# Ilumitunes-IR-String-Controller-v13.net
KiCad netlist of a schematic drawn in EAGLE
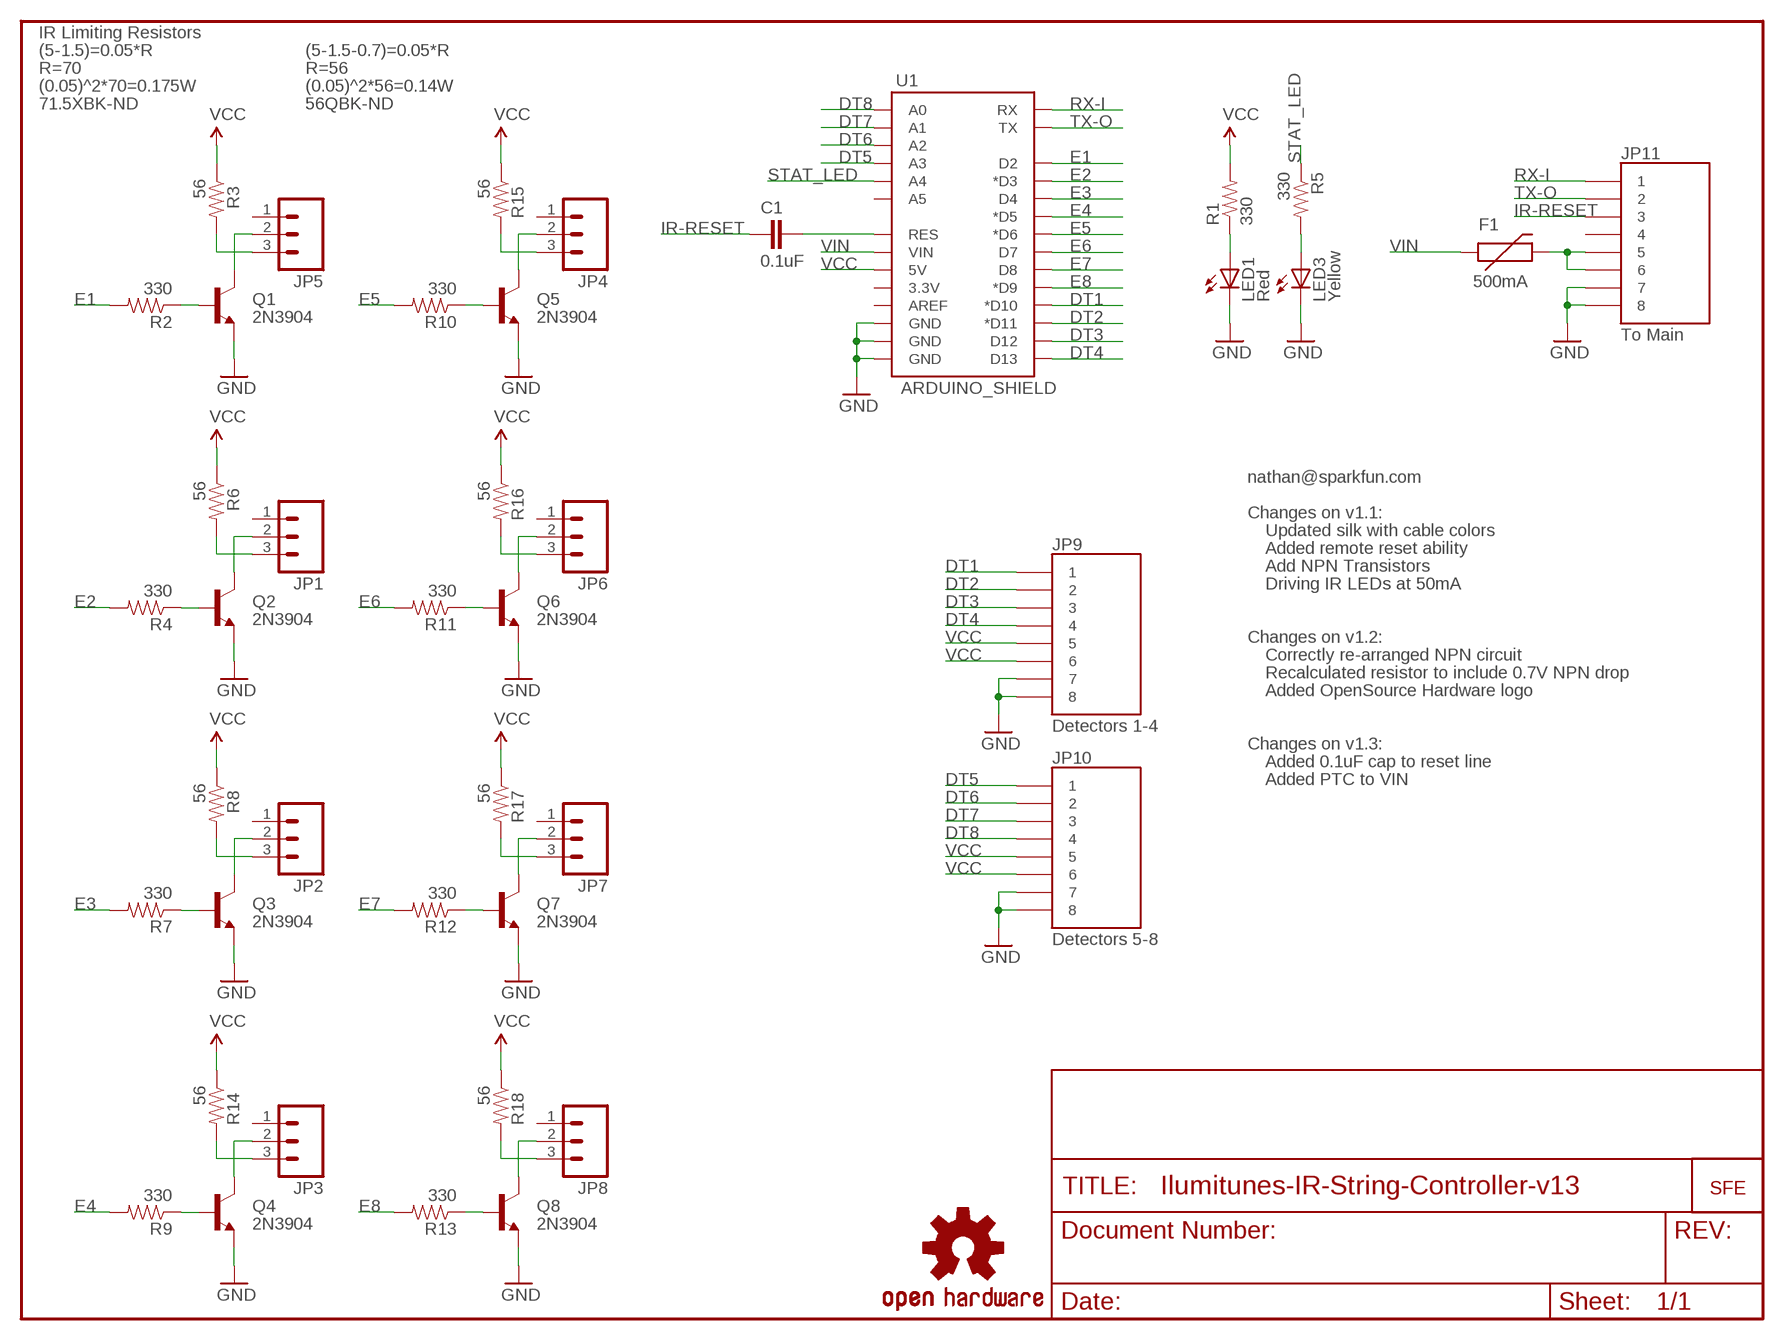
[diagram p0: schematic, sheet 1]

(export (version "E")
  (design (tool "Eeschema 10.0.6"))
  (components
    (comp (ref "C1")
      (value "0.1uF")
      (footprint "eagle-import:CAP-PTH-SMALL2")
      (libsource (lib "eagle-import") (part "CAPPTH2"))
    )
    (comp (ref "F1")
      (value "500mA")
      (footprint "eagle-import:PTC")
      (libsource (lib "eagle-import") (part "PTCPTH"))
    )
    (comp (ref "JP1")
      (value "M03JST-PTH-VERT")
      (footprint "eagle-import:JST-3-PTH-VERT")
      (libsource (lib "eagle-import") (part "M03JST-PTH-VERT"))
    )
    (comp (ref "JP2")
      (value "M03JST-PTH-VERT")
      (footprint "eagle-import:JST-3-PTH-VERT")
      (libsource (lib "eagle-import") (part "M03JST-PTH-VERT"))
    )
    (comp (ref "JP3")
      (value "M03JST-PTH-VERT")
      (footprint "eagle-import:JST-3-PTH-VERT")
      (libsource (lib "eagle-import") (part "M03JST-PTH-VERT"))
    )
    (comp (ref "JP4")
      (value "M03JST-PTH-VERT")
      (footprint "eagle-import:JST-3-PTH-VERT")
      (libsource (lib "eagle-import") (part "M03JST-PTH-VERT"))
    )
    (comp (ref "JP5")
      (value "M03JST-PTH-VERT")
      (footprint "eagle-import:JST-3-PTH-VERT")
      (libsource (lib "eagle-import") (part "M03JST-PTH-VERT"))
    )
    (comp (ref "JP6")
      (value "M03JST-PTH-VERT")
      (footprint "eagle-import:JST-3-PTH-VERT")
      (libsource (lib "eagle-import") (part "M03JST-PTH-VERT"))
    )
    (comp (ref "JP7")
      (value "M03JST-PTH-VERT")
      (footprint "eagle-import:JST-3-PTH-VERT")
      (libsource (lib "eagle-import") (part "M03JST-PTH-VERT"))
    )
    (comp (ref "JP8")
      (value "M03JST-PTH-VERT")
      (footprint "eagle-import:JST-3-PTH-VERT")
      (libsource (lib "eagle-import") (part "M03JST-PTH-VERT"))
    )
    (comp (ref "JP9")
      (value "Detectors 1-4")
      (footprint "eagle-import:RJ45-8")
      (libsource (lib "eagle-import") (part "RJ45-8PTH"))
    )
    (comp (ref "JP10")
      (value "Detectors 5-8")
      (footprint "eagle-import:RJ45-8")
      (libsource (lib "eagle-import") (part "RJ45-8PTH"))
    )
    (comp (ref "JP11")
      (value "To Main")
      (footprint "eagle-import:RJ45-8")
      (libsource (lib "eagle-import") (part "RJ45-8PTH"))
    )
    (comp (ref "LED1")
      (value "Red")
      (footprint "eagle-import:LED5MM")
      (libsource (lib "eagle-import") (part "LED5MM"))
    )
    (comp (ref "LED3")
      (value "Yellow")
      (footprint "eagle-import:LED5MM")
      (libsource (lib "eagle-import") (part "LED5MM"))
    )
    (comp (ref "Q1")
      (value "2N3904")
      (footprint "eagle-import:TO-92")
      (libsource (lib "eagle-import") (part "TRANSISTOR_NPNTO92"))
    )
    (comp (ref "Q2")
      (value "2N3904")
      (footprint "eagle-import:TO-92")
      (libsource (lib "eagle-import") (part "TRANSISTOR_NPNTO92"))
    )
    (comp (ref "Q3")
      (value "2N3904")
      (footprint "eagle-import:TO-92")
      (libsource (lib "eagle-import") (part "TRANSISTOR_NPNTO92"))
    )
    (comp (ref "Q4")
      (value "2N3904")
      (footprint "eagle-import:TO-92")
      (libsource (lib "eagle-import") (part "TRANSISTOR_NPNTO92"))
    )
    (comp (ref "Q5")
      (value "2N3904")
      (footprint "eagle-import:TO-92")
      (libsource (lib "eagle-import") (part "TRANSISTOR_NPNTO92"))
    )
    (comp (ref "Q6")
      (value "2N3904")
      (footprint "eagle-import:TO-92")
      (libsource (lib "eagle-import") (part "TRANSISTOR_NPNTO92"))
    )
    (comp (ref "Q7")
      (value "2N3904")
      (footprint "eagle-import:TO-92")
      (libsource (lib "eagle-import") (part "TRANSISTOR_NPNTO92"))
    )
    (comp (ref "Q8")
      (value "2N3904")
      (footprint "eagle-import:TO-92")
      (libsource (lib "eagle-import") (part "TRANSISTOR_NPNTO92"))
    )
    (comp (ref "R1")
      (value "330")
      (footprint "eagle-import:AXIAL-0.3")
      (libsource (lib "eagle-import") (part "RESISTORAXIAL-0.3"))
    )
    (comp (ref "R2")
      (value "330")
      (footprint "eagle-import:AXIAL-0.3")
      (libsource (lib "eagle-import") (part "RESISTORAXIAL-0.3"))
    )
    (comp (ref "R3")
      (value "56")
      (footprint "eagle-import:AXIAL-0.3")
      (libsource (lib "eagle-import") (part "RESISTORAXIAL-0.3"))
    )
    (comp (ref "R4")
      (value "330")
      (footprint "eagle-import:AXIAL-0.3")
      (libsource (lib "eagle-import") (part "RESISTORAXIAL-0.3"))
    )
    (comp (ref "R5")
      (value "330")
      (footprint "eagle-import:AXIAL-0.3")
      (libsource (lib "eagle-import") (part "RESISTORAXIAL-0.3"))
    )
    (comp (ref "R6")
      (value "56")
      (footprint "eagle-import:AXIAL-0.3")
      (libsource (lib "eagle-import") (part "RESISTORAXIAL-0.3"))
    )
    (comp (ref "R7")
      (value "330")
      (footprint "eagle-import:AXIAL-0.3")
      (libsource (lib "eagle-import") (part "RESISTORAXIAL-0.3"))
    )
    (comp (ref "R8")
      (value "56")
      (footprint "eagle-import:AXIAL-0.3")
      (libsource (lib "eagle-import") (part "RESISTORAXIAL-0.3"))
    )
    (comp (ref "R9")
      (value "330")
      (footprint "eagle-import:AXIAL-0.3")
      (libsource (lib "eagle-import") (part "RESISTORAXIAL-0.3"))
    )
    (comp (ref "R10")
      (value "330")
      (footprint "eagle-import:AXIAL-0.3")
      (libsource (lib "eagle-import") (part "RESISTORAXIAL-0.3"))
    )
    (comp (ref "R11")
      (value "330")
      (footprint "eagle-import:AXIAL-0.3")
      (libsource (lib "eagle-import") (part "RESISTORAXIAL-0.3"))
    )
    (comp (ref "R12")
      (value "330")
      (footprint "eagle-import:AXIAL-0.3")
      (libsource (lib "eagle-import") (part "RESISTORAXIAL-0.3"))
    )
    (comp (ref "R13")
      (value "330")
      (footprint "eagle-import:AXIAL-0.3")
      (libsource (lib "eagle-import") (part "RESISTORAXIAL-0.3"))
    )
    (comp (ref "R14")
      (value "56")
      (footprint "eagle-import:AXIAL-0.3")
      (libsource (lib "eagle-import") (part "RESISTORAXIAL-0.3"))
    )
    (comp (ref "R15")
      (value "56")
      (footprint "eagle-import:AXIAL-0.3")
      (libsource (lib "eagle-import") (part "RESISTORAXIAL-0.3"))
    )
    (comp (ref "R16")
      (value "56")
      (footprint "eagle-import:AXIAL-0.3")
      (libsource (lib "eagle-import") (part "RESISTORAXIAL-0.3"))
    )
    (comp (ref "R17")
      (value "56")
      (footprint "eagle-import:AXIAL-0.3")
      (libsource (lib "eagle-import") (part "RESISTORAXIAL-0.3"))
    )
    (comp (ref "R18")
      (value "56")
      (footprint "eagle-import:AXIAL-0.3")
      (libsource (lib "eagle-import") (part "RESISTORAXIAL-0.3"))
    )
    (comp (ref "U$1")
      (value "LOGO-SFENEW")
      (footprint "eagle-import:SFE-NEW-WEBLOGO")
      (libsource (lib "eagle-import") (part "LOGO-SFENEW"))
    )
    (comp (ref "U$3")
      (value "OSHW-LOGOS")
      (footprint "eagle-import:OSHW-LOGO-S")
      (libsource (lib "eagle-import") (part "OSHW-LOGOS"))
    )
    (comp (ref "U1")
      (value "ARDUINO_SHIELD")
      (footprint "eagle-import:DUEMILANOVE_SHIELD_NOHOLES")
      (libsource (lib "eagle-import") (part "ARDUINO_SHIELDNOHOLES"))
    )
  )
  (nets
    (net (code "1") (name "/DT1") (class "Default")
      (node (ref "JP9") (pin "1") (pinfunction "1_1") (pintype "bidirectional"))
      (node (ref "U1") (pin "D10") (pinfunction "*D10_D10") (pintype "bidirectional"))
    )
    (net (code "2") (name "/DT2") (class "Default")
      (node (ref "JP9") (pin "2") (pinfunction "2_2") (pintype "bidirectional"))
      (node (ref "U1") (pin "D11") (pinfunction "*D11_D11") (pintype "bidirectional"))
    )
    (net (code "3") (name "/DT3") (class "Default")
      (node (ref "JP9") (pin "3") (pinfunction "3_3") (pintype "bidirectional"))
      (node (ref "U1") (pin "D12") (pinfunction "D12_D12") (pintype "bidirectional"))
    )
    (net (code "4") (name "/DT4") (class "Default")
      (node (ref "JP9") (pin "4") (pinfunction "4_4") (pintype "bidirectional"))
      (node (ref "U1") (pin "D13") (pinfunction "D13_D13") (pintype "bidirectional"))
    )
    (net (code "5") (name "/DT5") (class "Default")
      (node (ref "JP10") (pin "1") (pinfunction "1_1") (pintype "bidirectional"))
      (node (ref "U1") (pin "A3") (pinfunction "A3_A3") (pintype "bidirectional"))
    )
    (net (code "6") (name "/DT6") (class "Default")
      (node (ref "JP10") (pin "2") (pinfunction "2_2") (pintype "bidirectional"))
      (node (ref "U1") (pin "A2") (pinfunction "A2_A2") (pintype "bidirectional"))
    )
    (net (code "7") (name "/DT7") (class "Default")
      (node (ref "JP10") (pin "3") (pinfunction "3_3") (pintype "bidirectional"))
      (node (ref "U1") (pin "A1") (pinfunction "A1_A1") (pintype "bidirectional"))
    )
    (net (code "8") (name "/DT8") (class "Default")
      (node (ref "JP10") (pin "4") (pinfunction "4_4") (pintype "bidirectional"))
      (node (ref "U1") (pin "A0") (pinfunction "A0_A0") (pintype "bidirectional"))
    )
    (net (code "9") (name "/E1") (class "Default")
      (node (ref "R2") (pin "P$2") (pinfunction "2_P$2") (pintype "passive"))
      (node (ref "U1") (pin "D2") (pinfunction "D2_D2") (pintype "bidirectional"))
    )
    (net (code "10") (name "/E2") (class "Default")
      (node (ref "R4") (pin "P$2") (pinfunction "2_P$2") (pintype "passive"))
      (node (ref "U1") (pin "D3") (pinfunction "*D3_D3") (pintype "bidirectional"))
    )
    (net (code "11") (name "/E3") (class "Default")
      (node (ref "R7") (pin "P$2") (pinfunction "2_P$2") (pintype "passive"))
      (node (ref "U1") (pin "D4") (pinfunction "D4_D4") (pintype "bidirectional"))
    )
    (net (code "12") (name "/E4") (class "Default")
      (node (ref "R9") (pin "P$2") (pinfunction "2_P$2") (pintype "passive"))
      (node (ref "U1") (pin "D5") (pinfunction "*D5_D5") (pintype "bidirectional"))
    )
    (net (code "13") (name "/E5") (class "Default")
      (node (ref "R10") (pin "P$2") (pinfunction "2_P$2") (pintype "passive"))
      (node (ref "U1") (pin "D6") (pinfunction "*D6_D6") (pintype "bidirectional"))
    )
    (net (code "14") (name "/E6") (class "Default")
      (node (ref "R11") (pin "P$2") (pinfunction "2_P$2") (pintype "passive"))
      (node (ref "U1") (pin "D7") (pinfunction "D7_D7") (pintype "bidirectional"))
    )
    (net (code "15") (name "/E7") (class "Default")
      (node (ref "R12") (pin "P$2") (pinfunction "2_P$2") (pintype "passive"))
      (node (ref "U1") (pin "D8") (pinfunction "D8_D8") (pintype "bidirectional"))
    )
    (net (code "16") (name "/E8") (class "Default")
      (node (ref "R13") (pin "P$2") (pinfunction "2_P$2") (pintype "passive"))
      (node (ref "U1") (pin "D9") (pinfunction "*D9_D9") (pintype "bidirectional"))
    )
    (net (code "17") (name "/IR-RESET") (class "Default")
      (node (ref "C1") (pin "1") (pinfunction "1_1") (pintype "passive"))
      (node (ref "JP11") (pin "3") (pinfunction "3_3") (pintype "bidirectional"))
    )
    (net (code "18") (name "/RX-I") (class "Default")
      (node (ref "JP11") (pin "1") (pinfunction "1_1") (pintype "bidirectional"))
      (node (ref "U1") (pin "RX") (pinfunction "RX_RX") (pintype "bidirectional"))
    )
    (net (code "19") (name "/STAT_LED") (class "Default")
      (node (ref "R5") (pin "P$1") (pinfunction "1_P$1") (pintype "passive"))
      (node (ref "U1") (pin "A4") (pinfunction "A4_A4") (pintype "bidirectional"))
    )
    (net (code "20") (name "/TX-O") (class "Default")
      (node (ref "JP11") (pin "2") (pinfunction "2_2") (pintype "bidirectional"))
      (node (ref "U1") (pin "TX") (pinfunction "TX_TX") (pintype "bidirectional"))
    )
    (net (code "21") (name "/VIN") (class "Default")
      (node (ref "F1") (pin "P$1") (pinfunction "1_P$1") (pintype "bidirectional"))
      (node (ref "U1") (pin "VIN") (pinfunction "VIN_VIN") (pintype "bidirectional"))
    )
    (net (code "22") (name "GND") (class "Default")
      (node (ref "JP10") (pin "7") (pinfunction "7_7") (pintype "bidirectional"))
      (node (ref "JP10") (pin "8") (pinfunction "8_8") (pintype "bidirectional"))
      (node (ref "JP11") (pin "7") (pinfunction "7_7") (pintype "bidirectional"))
      (node (ref "JP11") (pin "8") (pinfunction "8_8") (pintype "bidirectional"))
      (node (ref "JP9") (pin "7") (pinfunction "7_7") (pintype "bidirectional"))
      (node (ref "JP9") (pin "8") (pinfunction "8_8") (pintype "bidirectional"))
      (node (ref "LED1") (pin "K") (pinfunction "C_K") (pintype "passive"))
      (node (ref "LED3") (pin "K") (pinfunction "C_K") (pintype "passive"))
      (node (ref "Q1") (pin "1") (pinfunction "E_1") (pintype "passive"))
      (node (ref "Q2") (pin "1") (pinfunction "E_1") (pintype "passive"))
      (node (ref "Q3") (pin "1") (pinfunction "E_1") (pintype "passive"))
      (node (ref "Q4") (pin "1") (pinfunction "E_1") (pintype "passive"))
      (node (ref "Q5") (pin "1") (pinfunction "E_1") (pintype "passive"))
      (node (ref "Q6") (pin "1") (pinfunction "E_1") (pintype "passive"))
      (node (ref "Q7") (pin "1") (pinfunction "E_1") (pintype "passive"))
      (node (ref "Q8") (pin "1") (pinfunction "E_1") (pintype "passive"))
      (node (ref "U1") (pin "GND@0") (pinfunction "GND_GND@0") (pintype "bidirectional"))
      (node (ref "U1") (pin "GND@1") (pinfunction "GND_GND@1") (pintype "bidirectional"))
      (node (ref "U1") (pin "GND@2") (pinfunction "GND_GND@2") (pintype "bidirectional"))
    )
    (net (code "23") (name "Net-(C1-Pad2)") (class "Default")
      (node (ref "C1") (pin "2") (pinfunction "2_2") (pintype "passive"))
      (node (ref "U1") (pin "RES") (pinfunction "RES_RES") (pintype "bidirectional"))
    )
    (net (code "24") (name "Net-(F1-2)") (class "Default")
      (node (ref "F1") (pin "P$2") (pinfunction "2_P$2") (pintype "bidirectional"))
      (node (ref "JP11") (pin "5") (pinfunction "5_5") (pintype "bidirectional"))
      (node (ref "JP11") (pin "6") (pinfunction "6_6") (pintype "bidirectional"))
    )
    (net (code "25") (name "Net-(Q1-B)") (class "Default")
      (node (ref "Q1") (pin "2") (pinfunction "B_2") (pintype "passive"))
      (node (ref "R2") (pin "P$1") (pinfunction "1_P$1") (pintype "passive"))
    )
    (net (code "26") (name "Net-(Q1-C)") (class "Default")
      (node (ref "JP5") (pin "2") (pinfunction "2_2") (pintype "passive"))
      (node (ref "Q1") (pin "3") (pinfunction "C_3") (pintype "passive"))
    )
    (net (code "27") (name "Net-(Q2-B)") (class "Default")
      (node (ref "Q2") (pin "2") (pinfunction "B_2") (pintype "passive"))
      (node (ref "R4") (pin "P$1") (pinfunction "1_P$1") (pintype "passive"))
    )
    (net (code "28") (name "Net-(Q2-C)") (class "Default")
      (node (ref "JP1") (pin "2") (pinfunction "2_2") (pintype "passive"))
      (node (ref "Q2") (pin "3") (pinfunction "C_3") (pintype "passive"))
    )
    (net (code "29") (name "Net-(Q3-B)") (class "Default")
      (node (ref "Q3") (pin "2") (pinfunction "B_2") (pintype "passive"))
      (node (ref "R7") (pin "P$1") (pinfunction "1_P$1") (pintype "passive"))
    )
    (net (code "30") (name "Net-(Q3-C)") (class "Default")
      (node (ref "JP2") (pin "2") (pinfunction "2_2") (pintype "passive"))
      (node (ref "Q3") (pin "3") (pinfunction "C_3") (pintype "passive"))
    )
    (net (code "31") (name "Net-(Q4-B)") (class "Default")
      (node (ref "Q4") (pin "2") (pinfunction "B_2") (pintype "passive"))
      (node (ref "R9") (pin "P$1") (pinfunction "1_P$1") (pintype "passive"))
    )
    (net (code "32") (name "Net-(Q4-C)") (class "Default")
      (node (ref "JP3") (pin "2") (pinfunction "2_2") (pintype "passive"))
      (node (ref "Q4") (pin "3") (pinfunction "C_3") (pintype "passive"))
    )
    (net (code "33") (name "Net-(Q5-B)") (class "Default")
      (node (ref "Q5") (pin "2") (pinfunction "B_2") (pintype "passive"))
      (node (ref "R10") (pin "P$1") (pinfunction "1_P$1") (pintype "passive"))
    )
    (net (code "34") (name "Net-(Q5-C)") (class "Default")
      (node (ref "JP4") (pin "2") (pinfunction "2_2") (pintype "passive"))
      (node (ref "Q5") (pin "3") (pinfunction "C_3") (pintype "passive"))
    )
    (net (code "35") (name "Net-(Q6-B)") (class "Default")
      (node (ref "Q6") (pin "2") (pinfunction "B_2") (pintype "passive"))
      (node (ref "R11") (pin "P$1") (pinfunction "1_P$1") (pintype "passive"))
    )
    (net (code "36") (name "Net-(Q6-C)") (class "Default")
      (node (ref "JP6") (pin "2") (pinfunction "2_2") (pintype "passive"))
      (node (ref "Q6") (pin "3") (pinfunction "C_3") (pintype "passive"))
    )
    (net (code "37") (name "Net-(Q7-B)") (class "Default")
      (node (ref "Q7") (pin "2") (pinfunction "B_2") (pintype "passive"))
      (node (ref "R12") (pin "P$1") (pinfunction "1_P$1") (pintype "passive"))
    )
    (net (code "38") (name "Net-(Q7-C)") (class "Default")
      (node (ref "JP7") (pin "2") (pinfunction "2_2") (pintype "passive"))
      (node (ref "Q7") (pin "3") (pinfunction "C_3") (pintype "passive"))
    )
    (net (code "39") (name "Net-(Q8-B)") (class "Default")
      (node (ref "Q8") (pin "2") (pinfunction "B_2") (pintype "passive"))
      (node (ref "R13") (pin "P$1") (pinfunction "1_P$1") (pintype "passive"))
    )
    (net (code "40") (name "Net-(Q8-C)") (class "Default")
      (node (ref "JP8") (pin "2") (pinfunction "2_2") (pintype "passive"))
      (node (ref "Q8") (pin "3") (pinfunction "C_3") (pintype "passive"))
    )
    (net (code "41") (name "Net-(R1-1)") (class "Default")
      (node (ref "LED1") (pin "A") (pinfunction "A_A") (pintype "passive"))
      (node (ref "R1") (pin "P$1") (pinfunction "1_P$1") (pintype "passive"))
    )
    (net (code "42") (name "Net-(R3-2)") (class "Default")
      (node (ref "JP5") (pin "3") (pinfunction "3_3") (pintype "passive"))
      (node (ref "R3") (pin "P$2") (pinfunction "2_P$2") (pintype "passive"))
    )
    (net (code "43") (name "Net-(R5-2)") (class "Default")
      (node (ref "LED3") (pin "A") (pinfunction "A_A") (pintype "passive"))
      (node (ref "R5") (pin "P$2") (pinfunction "2_P$2") (pintype "passive"))
    )
    (net (code "44") (name "Net-(R6-2)") (class "Default")
      (node (ref "JP1") (pin "3") (pinfunction "3_3") (pintype "passive"))
      (node (ref "R6") (pin "P$2") (pinfunction "2_P$2") (pintype "passive"))
    )
    (net (code "45") (name "Net-(R8-2)") (class "Default")
      (node (ref "JP2") (pin "3") (pinfunction "3_3") (pintype "passive"))
      (node (ref "R8") (pin "P$2") (pinfunction "2_P$2") (pintype "passive"))
    )
    (net (code "46") (name "Net-(R14-2)") (class "Default")
      (node (ref "JP3") (pin "3") (pinfunction "3_3") (pintype "passive"))
      (node (ref "R14") (pin "P$2") (pinfunction "2_P$2") (pintype "passive"))
    )
    (net (code "47") (name "Net-(R15-2)") (class "Default")
      (node (ref "JP4") (pin "3") (pinfunction "3_3") (pintype "passive"))
      (node (ref "R15") (pin "P$2") (pinfunction "2_P$2") (pintype "passive"))
    )
    (net (code "48") (name "Net-(R16-2)") (class "Default")
      (node (ref "JP6") (pin "3") (pinfunction "3_3") (pintype "passive"))
      (node (ref "R16") (pin "P$2") (pinfunction "2_P$2") (pintype "passive"))
    )
    (net (code "49") (name "Net-(R17-2)") (class "Default")
      (node (ref "JP7") (pin "3") (pinfunction "3_3") (pintype "passive"))
      (node (ref "R17") (pin "P$2") (pinfunction "2_P$2") (pintype "passive"))
    )
    (net (code "50") (name "Net-(R18-2)") (class "Default")
      (node (ref "JP8") (pin "3") (pinfunction "3_3") (pintype "passive"))
      (node (ref "R18") (pin "P$2") (pinfunction "2_P$2") (pintype "passive"))
    )
    (net (code "51") (name "VCC") (class "Default")
      (node (ref "JP10") (pin "5") (pinfunction "5_5") (pintype "bidirectional"))
      (node (ref "JP10") (pin "6") (pinfunction "6_6") (pintype "bidirectional"))
      (node (ref "JP9") (pin "5") (pinfunction "5_5") (pintype "bidirectional"))
      (node (ref "JP9") (pin "6") (pinfunction "6_6") (pintype "bidirectional"))
      (node (ref "R1") (pin "P$2") (pinfunction "2_P$2") (pintype "passive"))
      (node (ref "R14") (pin "P$1") (pinfunction "1_P$1") (pintype "passive"))
      (node (ref "R15") (pin "P$1") (pinfunction "1_P$1") (pintype "passive"))
      (node (ref "R16") (pin "P$1") (pinfunction "1_P$1") (pintype "passive"))
      (node (ref "R17") (pin "P$1") (pinfunction "1_P$1") (pintype "passive"))
      (node (ref "R18") (pin "P$1") (pinfunction "1_P$1") (pintype "passive"))
      (node (ref "R3") (pin "P$1") (pinfunction "1_P$1") (pintype "passive"))
      (node (ref "R6") (pin "P$1") (pinfunction "1_P$1") (pintype "passive"))
      (node (ref "R8") (pin "P$1") (pinfunction "1_P$1") (pintype "passive"))
      (node (ref "U1") (pin "5V") (pinfunction "5V_5V") (pintype "bidirectional"))
    )
    (net (code "52") (name "unconnected-(JP1-Pad1)") (class "Default")
      (node (ref "JP1") (pin "1") (pinfunction "1_1") (pintype "passive"))
    )
    (net (code "53") (name "unconnected-(JP2-Pad1)") (class "Default")
      (node (ref "JP2") (pin "1") (pinfunction "1_1") (pintype "passive"))
    )
    (net (code "54") (name "unconnected-(JP3-Pad1)") (class "Default")
      (node (ref "JP3") (pin "1") (pinfunction "1_1") (pintype "passive"))
    )
    (net (code "55") (name "unconnected-(JP4-Pad1)") (class "Default")
      (node (ref "JP4") (pin "1") (pinfunction "1_1") (pintype "passive"))
    )
    (net (code "56") (name "unconnected-(JP5-Pad1)") (class "Default")
      (node (ref "JP5") (pin "1") (pinfunction "1_1") (pintype "passive"))
    )
    (net (code "57") (name "unconnected-(JP6-Pad1)") (class "Default")
      (node (ref "JP6") (pin "1") (pinfunction "1_1") (pintype "passive"))
    )
    (net (code "58") (name "unconnected-(JP7-Pad1)") (class "Default")
      (node (ref "JP7") (pin "1") (pinfunction "1_1") (pintype "passive"))
    )
    (net (code "59") (name "unconnected-(JP8-Pad1)") (class "Default")
      (node (ref "JP8") (pin "1") (pinfunction "1_1") (pintype "passive"))
    )
    (net (code "60") (name "unconnected-(JP11-Pad4)") (class "Default")
      (node (ref "JP11") (pin "4") (pinfunction "4_4") (pintype "bidirectional"))
    )
    (net (code "61") (name "unconnected-(U1-Pad3.3V)") (class "Default")
      (node (ref "U1") (pin "3.3V") (pinfunction "3.3V_3.3V") (pintype "bidirectional"))
    )
    (net (code "62") (name "unconnected-(U1-PadA5)") (class "Default")
      (node (ref "U1") (pin "A5") (pinfunction "A5_A5") (pintype "bidirectional"))
    )
    (net (code "63") (name "unconnected-(U1-PadAREF)") (class "Default")
      (node (ref "U1") (pin "AREF") (pinfunction "AREF_AREF") (pintype "bidirectional"))
    )
  )
)
